# 02_PowerProtections.net
KiCad netlist of a schematic drawn in Altium Designer
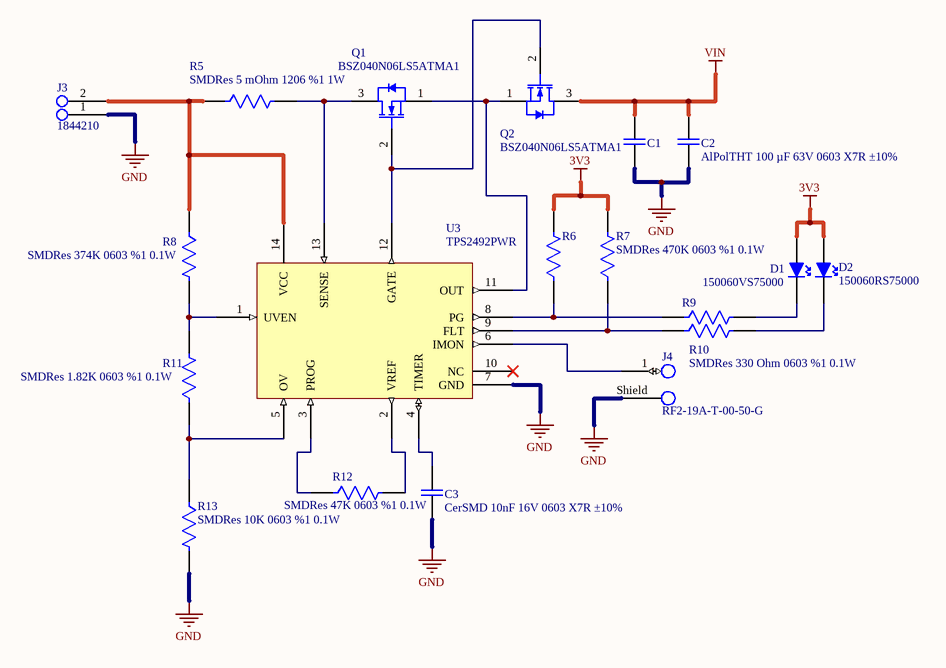
[diagram p0: [02]PowerProtections.SchDoc]

(export (version "E")
  (design (tool "Eeschema 10.0.6"))
  (components
    (comp (ref "C1")
      (value "AlPolTHT 100 µF 63V 0603 X7R ±10%")
      (footprint "107AVG063MFBJ")
      (description "Ceramic Capacitor SMD 100 µF 63V 0603 X7R ±10%")
      (fields (field (name "DIGI-KEY PART NUMBER") "1572-1656-ND") (field (name "VOLTAGE") "63V"))
      (libsource (lib "AGH Power Electronics Lab") (part "10 nF"))
    )
    (comp (ref "C2")
      (value "AlPolTHT 100 µF 63V 0603 X7R ±10%")
      (footprint "107AVG063MFBJ")
      (description "Ceramic Capacitor SMD 100 µF 63V 0603 X7R ±10%")
      (fields (field (name "DIGI-KEY PART NUMBER") "1572-1656-ND") (field (name "VOLTAGE") "63V"))
      (libsource (lib "AGH Power Electronics Lab") (part "10 nF"))
    )
    (comp (ref "C3")
      (value "CerSMD 10nF 16V 0603 X7R ±10%")
      (footprint "CAPC1608X09N")
      (description "Ceramic Capacitor SMD  10nF 16V 0603 X7R ±10%")
      (fields
        (field (name "DIGI-KEY PART NUMBER") "1276-CL10B103KO8WPNCCT-ND")
        (field (name "VOLTAGE") "16V")
      )
      (libsource (lib "AGH Power Electronics Lab") (part "10 nF"))
    )
    (comp (ref "D1")
      (value "150060VS75000")
      (footprint "LED1608X08N")
      (description "GREEN LED 0603")
      (libsource (lib "AGH Power Electronics Lab") (part "LED"))
    )
    (comp (ref "D2")
      (value "150060RS75000")
      (footprint "LED1608X08N")
      (description "RED LED 0603")
      (libsource (lib "AGH Power Electronics Lab") (part "LED"))
    )
    (comp (ref "J3")
      (value "1844210")
      (footprint "1844210")
      (description "12A 2-Pos, Right Angle")
      (libsource (lib "AGH Power Electronics Lab") (part "1844210"))
    )
    (comp (ref "J4")
      (value "RF2-19A-T-00-50-G")
      (footprint "RF2-19A-T-00-50-G")
      (description "Rf Sma Connector")
      (libsource (lib "AGH Power Electronics Lab") (part "RF2-19A-T-00-50-G"))
    )
    (comp (ref "Q1")
      (value "BSZ040N06LS5ATMA1")
      (footprint "PG-TSDSON-8-FL")
      (description "N-MOS 60V 17A (Ta) 101A (Tc)")
      (libsource (lib "AGH Power Electronics Lab") (part "N-MOS"))
    )
    (comp (ref "Q2")
      (value "BSZ040N06LS5ATMA1")
      (footprint "PG-TSDSON-8-FL")
      (description "N-MOS 60V 17A (Ta) 101A (Tc)")
      (libsource (lib "AGH Power Electronics Lab") (part "N-MOS"))
    )
    (comp (ref "R5")
      (value "SMDRes 5 mOhm 1206 %1 1W")
      (footprint "RESC3116X10N")
      (fields
        (field (name "DIGI-KEY PART NUMBER") "CSRF1206FT5L00CT-ND")
        (field (name "TOLERANCE") "±1%")
        (field (name "MOUSER PART NUMBER") "708-CSRF1206FT5L00")
      )
      (libsource (lib "AGH Power Electronics Lab") (part "Res Symbol"))
    )
    (comp (ref "R6")
      (value "SMDRes 470K 0603 %1 0.1W")
      (footprint "RESC1508X06N")
      (description "Res Thick Film 0603 470K Ohm 1% 0.1W(1/10W) ±100ppm/C Pad SMD T/R Automotive AEC-Q200")
      (fields (field (name "MOUSER PART NUMBER") "708-RMCF0603FT470K") (field (name "POWER") "0.1W"))
      (libsource (lib "AGH Power Electronics Lab") (part "Res Symbol"))
    )
    (comp (ref "R7")
      (value "SMDRes 470K 0603 %1 0.1W")
      (footprint "RESC1508X06N")
      (description "Res Thick Film 0603 470K Ohm 1% 0.1W(1/10W) ±100ppm/C Pad SMD T/R Automotive AEC-Q200")
      (fields (field (name "MOUSER PART NUMBER") "708-RMCF0603FT470K") (field (name "POWER") "0.1W"))
      (libsource (lib "AGH Power Electronics Lab") (part "Res Symbol"))
    )
    (comp (ref "R8")
      (value "SMDRes 374K 0603 %1 0.1W")
      (footprint "RESC1508X06N")
      (description "Res Thick Film 0603 374K Ohm 1% 0.1W(1/10W) ±100ppm/C Pad SMD T/R Automotive AEC-Q200")
      (fields (field (name "POWER") "0.1W") (field (name "MANUFACTURER") "Stackpole Electronics Inc"))
      (libsource (lib "AGH Power Electronics Lab") (part "Res Symbol"))
    )
    (comp (ref "R9")
      (value "MDRes 330 Ohm 0603 %1 0.1W")
      (footprint "RESC1508X06N")
      (description "Res Thick Film 0603 33 kOhm Ohm 1% 0.1W(1/10W) ±100ppm/C Pad SMD T/R Automotive AEC-Q200")
      (fields (field (name "MOUSER PART NUMBER") "708-RMCF0603FT330R") (field (name "TOLERANCE") "±1%"))
      (libsource (lib "AGH Power Electronics Lab") (part "2.2 Ohm"))
    )
    (comp (ref "R10")
      (value "SMDRes 330 Ohm 0603 %1 0.1W")
      (footprint "RESC1508X06N")
      (description "Res Thick Film 0603 33 kOhm Ohm 1% 0.1W(1/10W) ±100ppm/C Pad SMD T/R Automotive AEC-Q200")
      (fields (field (name "MOUSER PART NUMBER") "708-RMCF0603FT330R") (field (name "TOLERANCE") "±1%"))
      (libsource (lib "AGH Power Electronics Lab") (part "2.2 Ohm"))
    )
    (comp (ref "R11")
      (value "SMDRes 1.82K 0603 %1 0.1W")
      (footprint "RESC1508X06N")
      (description "Res Thick Film 0603 1.82K Ohm 1% 0.1W(1/10W) ±100ppm/C Pad SMD T/R Automotive AEC-Q200")
      (fields
        (field (name "MOUSER PART NUMBER") "708-RMCF0603FT1K82")
        (field (name "MANUFACTURER") "Stackpole Electronics Inc")
      )
      (libsource (lib "AGH Power Electronics Lab") (part "Res Symbol"))
    )
    (comp (ref "R12")
      (value "SMDRes 47K 0603 %1 0.1W")
      (footprint "RESC1508X06N")
      (description "Res Thick Film 0603 47K Ohm 1% 0.1W(1/10W) ±100ppm/C Pad SMD T/R Automotive AEC-Q200")
      (fields (field (name "POWER") "0.1W") (field (name "TOLERANCE") "±1%"))
      (libsource (lib "AGH Power Electronics Lab") (part "Res Symbol"))
    )
    (comp (ref "R13")
      (value "SMDRes 10K 0603 %1 0.1W")
      (footprint "RESC1508X06N")
      (description "Res Thick Film 0603 10K Ohm 1% 0.1W(1/10W) ±100ppm/C Pad SMD T/R Automotive AEC-Q200")
      (fields (field (name "POWER") "0.1W") (field (name "MOUSER PART NUMBER") "708-RMCF0603FT10K0"))
      (libsource (lib "AGH Power Electronics Lab") (part "Res Symbol"))
    )
    (comp (ref "U3")
      (value "TPS2492PWR")
      (footprint "TSOP65P640X120-14L")
      (description "eFuses - External MOSFETs - 9V-80V")
      (fields
        (field (name "MANUFACTURER") "Texas Instruments")
        (field (name "MOUSER PART NUMBER") "595-TPS2492PWR")
      )
      (libsource (lib "AGH Power Electronics Lab") (part "TPS2492PWR"))
    )
  )
  (nets
    (net (code "1") (name "3V3") (class "Default")
      (node (ref "D1") (pin "1") (pinfunction "A_1") (pintype "passive"))
      (node (ref "D2") (pin "1") (pinfunction "A_1") (pintype "passive"))
      (node (ref "R6") (pin "2") (pinfunction "2_2") (pintype "passive"))
      (node (ref "R7") (pin "2") (pinfunction "2_2") (pintype "passive"))
    )
    (net (code "2") (name "GND") (class "Default")
      (node (ref "C1") (pin "2") (pinfunction "2_2") (pintype "passive"))
      (node (ref "C2") (pin "2") (pinfunction "2_2") (pintype "passive"))
      (node (ref "C3") (pin "2") (pinfunction "2_2") (pintype "passive"))
      (node (ref "J3") (pin "1") (pinfunction "1_1") (pintype "power_in"))
      (node (ref "J4") (pin "Shield") (pinfunction "Shield_Shield") (pintype "power_in"))
      (node (ref "R13") (pin "2") (pinfunction "2_2") (pintype "passive"))
      (node (ref "U3") (pin "7") (pinfunction "GND_7") (pintype "power_in"))
    )
    (net (code "3") (name "Net-(D1-K)") (class "Default")
      (node (ref "D1") (pin "2") (pinfunction "K_2") (pintype "passive"))
      (node (ref "R9") (pin "2") (pinfunction "2_2") (pintype "passive"))
    )
    (net (code "4") (name "Net-(D2-K)") (class "Default")
      (node (ref "D2") (pin "2") (pinfunction "K_2") (pintype "passive"))
      (node (ref "R10") (pin "2") (pinfunction "2_2") (pintype "passive"))
    )
    (net (code "5") (name "Net-(Q1-D)") (class "Default")
      (node (ref "Q1") (pin "3") (pinfunction "D_3") (pintype "passive"))
      (node (ref "R5") (pin "2") (pinfunction "2_2") (pintype "passive"))
      (node (ref "U3") (pin "13") (pinfunction "SENSE_13") (pintype "input"))
    )
    (net (code "6") (name "Net-(Q1-G)") (class "Default")
      (node (ref "Q1") (pin "2") (pinfunction "G_2") (pintype "passive"))
      (node (ref "Q2") (pin "2") (pinfunction "G_2") (pintype "passive"))
      (node (ref "U3") (pin "12") (pinfunction "GATE_12") (pintype "output"))
    )
    (net (code "7") (name "Net-(Q1-S)") (class "Default")
      (node (ref "Q1") (pin "1") (pinfunction "S_1") (pintype "passive"))
      (node (ref "Q2") (pin "1") (pinfunction "S_1") (pintype "passive"))
      (node (ref "U3") (pin "11") (pinfunction "OUT_11") (pintype "output"))
    )
    (net (code "8") (name "Net-(U3-FLT)") (class "Default")
      (node (ref "R10") (pin "1") (pinfunction "1_1") (pintype "passive"))
      (node (ref "R7") (pin "1") (pinfunction "1_1") (pintype "passive"))
      (node (ref "U3") (pin "9") (pinfunction "FLT_9") (pintype "output"))
    )
    (net (code "9") (name "Net-(U3-IMON)") (class "Default")
      (node (ref "J4") (pin "1") (pinfunction "1_1") (pintype "bidirectional"))
      (node (ref "U3") (pin "6") (pinfunction "IMON_6") (pintype "output"))
    )
    (net (code "10") (name "Net-(U3-OV)") (class "Default")
      (node (ref "R11") (pin "1") (pinfunction "1_1") (pintype "passive"))
      (node (ref "R13") (pin "1") (pinfunction "1_1") (pintype "passive"))
      (node (ref "U3") (pin "5") (pinfunction "OV_5") (pintype "input"))
    )
    (net (code "11") (name "Net-(U3-PG)") (class "Default")
      (node (ref "R6") (pin "1") (pinfunction "1_1") (pintype "passive"))
      (node (ref "R9") (pin "1") (pinfunction "1_1") (pintype "passive"))
      (node (ref "U3") (pin "8") (pinfunction "PG_8") (pintype "output"))
    )
    (net (code "12") (name "Net-(U3-PROG)") (class "Default")
      (node (ref "R12") (pin "1") (pinfunction "1_1") (pintype "passive"))
      (node (ref "U3") (pin "3") (pinfunction "PROG_3") (pintype "input"))
    )
    (net (code "13") (name "Net-(U3-TIMER)") (class "Default")
      (node (ref "C3") (pin "1") (pinfunction "1_1") (pintype "passive"))
      (node (ref "U3") (pin "4") (pinfunction "TIMER_4") (pintype "bidirectional"))
    )
    (net (code "14") (name "Net-(U3-UVEN)") (class "Default")
      (node (ref "R11") (pin "2") (pinfunction "2_2") (pintype "passive"))
      (node (ref "R8") (pin "2") (pinfunction "2_2") (pintype "passive"))
      (node (ref "U3") (pin "1") (pinfunction "UVEN_1") (pintype "input"))
    )
    (net (code "15") (name "Net-(U3-VCC)") (class "Default")
      (node (ref "J3") (pin "2") (pinfunction "2_2") (pintype "power_in"))
      (node (ref "R5") (pin "1") (pinfunction "1_1") (pintype "passive"))
      (node (ref "R8") (pin "1") (pinfunction "1_1") (pintype "passive"))
      (node (ref "U3") (pin "14") (pinfunction "VCC_14") (pintype "power_in"))
    )
    (net (code "16") (name "Net-(U3-VREF)") (class "Default")
      (node (ref "R12") (pin "2") (pinfunction "2_2") (pintype "passive"))
      (node (ref "U3") (pin "2") (pinfunction "VREF_2") (pintype "output"))
    )
    (net (code "17") (name "VIN") (class "Default")
      (node (ref "C1") (pin "1") (pinfunction "1_1") (pintype "passive"))
      (node (ref "C2") (pin "1") (pinfunction "1_1") (pintype "passive"))
      (node (ref "Q2") (pin "3") (pinfunction "D_3") (pintype "passive"))
    )
    (net (code "18") (name "unconnected-(U3-NC-Pad10)") (class "Default")
      (node (ref "U3") (pin "10") (pinfunction "NC_10") (pintype "passive+no_connect"))
    )
  )
)
